# RPiEvm.net
KiCad netlist of a schematic drawn in EAGLE
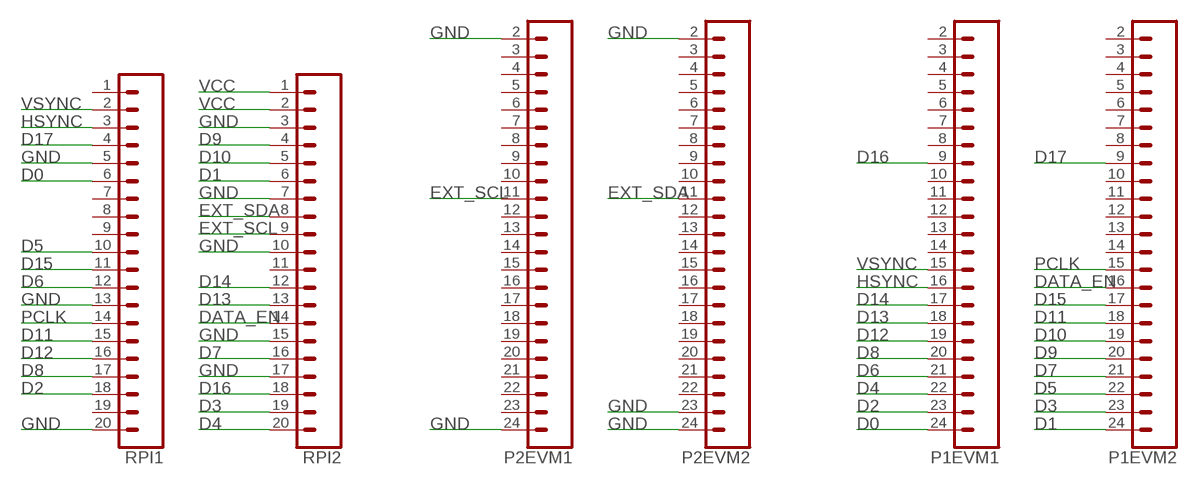
[diagram p0: schematic, sheet 1]

(export (version "E")
  (design (tool "Eeschema 10.0.6"))
  (components
    (comp (ref "P1EVM1")
      (value "CONN_23")
      (footprint "eagle-import:1X23")
      (libsource (lib "eagle-import") (part "CONN_23"))
    )
    (comp (ref "P1EVM2")
      (value "CONN_23")
      (footprint "eagle-import:1X23")
      (libsource (lib "eagle-import") (part "CONN_23"))
    )
    (comp (ref "P2EVM1")
      (value "CONN_23")
      (footprint "eagle-import:1X23")
      (libsource (lib "eagle-import") (part "CONN_23"))
    )
    (comp (ref "P2EVM2")
      (value "CONN_23")
      (footprint "eagle-import:1X23")
      (libsource (lib "eagle-import") (part "CONN_23"))
    )
    (comp (ref "RPI1")
      (value "CONN_20")
      (footprint "eagle-import:1X20")
      (libsource (lib "eagle-import") (part "CONN_20"))
    )
    (comp (ref "RPI2")
      (value "CONN_20")
      (footprint "eagle-import:1X20")
      (libsource (lib "eagle-import") (part "CONN_20"))
    )
  )
  (nets
    (net (code "1") (name "/D0") (class "Default")
      (node (ref "P1EVM1") (pin "24") (pinfunction "24_24") (pintype "passive"))
      (node (ref "RPI1") (pin "6") (pinfunction "6_6") (pintype "passive"))
    )
    (net (code "2") (name "/D1") (class "Default")
      (node (ref "P1EVM2") (pin "24") (pinfunction "24_24") (pintype "passive"))
      (node (ref "RPI2") (pin "6") (pinfunction "6_6") (pintype "passive"))
    )
    (net (code "3") (name "/D2") (class "Default")
      (node (ref "P1EVM1") (pin "23") (pinfunction "23_23") (pintype "passive"))
      (node (ref "RPI1") (pin "18") (pinfunction "18_18") (pintype "passive"))
    )
    (net (code "4") (name "/D3") (class "Default")
      (node (ref "P1EVM2") (pin "23") (pinfunction "23_23") (pintype "passive"))
      (node (ref "RPI2") (pin "19") (pinfunction "19_19") (pintype "passive"))
    )
    (net (code "5") (name "/D4") (class "Default")
      (node (ref "P1EVM1") (pin "22") (pinfunction "22_22") (pintype "passive"))
      (node (ref "RPI2") (pin "20") (pinfunction "20_20") (pintype "passive"))
    )
    (net (code "6") (name "/D5") (class "Default")
      (node (ref "P1EVM2") (pin "22") (pinfunction "22_22") (pintype "passive"))
      (node (ref "RPI1") (pin "10") (pinfunction "10_10") (pintype "passive"))
    )
    (net (code "7") (name "/D6") (class "Default")
      (node (ref "P1EVM1") (pin "21") (pinfunction "21_21") (pintype "passive"))
      (node (ref "RPI1") (pin "12") (pinfunction "12_12") (pintype "passive"))
    )
    (net (code "8") (name "/D7") (class "Default")
      (node (ref "P1EVM2") (pin "21") (pinfunction "21_21") (pintype "passive"))
      (node (ref "RPI2") (pin "16") (pinfunction "16_16") (pintype "passive"))
    )
    (net (code "9") (name "/D8") (class "Default")
      (node (ref "P1EVM1") (pin "20") (pinfunction "20_20") (pintype "passive"))
      (node (ref "RPI1") (pin "17") (pinfunction "17_17") (pintype "passive"))
    )
    (net (code "10") (name "/D9") (class "Default")
      (node (ref "P1EVM2") (pin "20") (pinfunction "20_20") (pintype "passive"))
      (node (ref "RPI2") (pin "4") (pinfunction "4_4") (pintype "passive"))
    )
    (net (code "11") (name "/D10") (class "Default")
      (node (ref "P1EVM2") (pin "19") (pinfunction "19_19") (pintype "passive"))
      (node (ref "RPI2") (pin "5") (pinfunction "5_5") (pintype "passive"))
    )
    (net (code "12") (name "/D11") (class "Default")
      (node (ref "P1EVM2") (pin "18") (pinfunction "18_18") (pintype "passive"))
      (node (ref "RPI1") (pin "15") (pinfunction "15_15") (pintype "passive"))
    )
    (net (code "13") (name "/D12") (class "Default")
      (node (ref "P1EVM1") (pin "19") (pinfunction "19_19") (pintype "passive"))
      (node (ref "RPI1") (pin "16") (pinfunction "16_16") (pintype "passive"))
    )
    (net (code "14") (name "/D13") (class "Default")
      (node (ref "P1EVM1") (pin "18") (pinfunction "18_18") (pintype "passive"))
      (node (ref "RPI2") (pin "13") (pinfunction "13_13") (pintype "passive"))
    )
    (net (code "15") (name "/D14") (class "Default")
      (node (ref "P1EVM1") (pin "17") (pinfunction "17_17") (pintype "passive"))
      (node (ref "RPI2") (pin "12") (pinfunction "12_12") (pintype "passive"))
    )
    (net (code "16") (name "/D15") (class "Default")
      (node (ref "P1EVM2") (pin "17") (pinfunction "17_17") (pintype "passive"))
      (node (ref "RPI1") (pin "11") (pinfunction "11_11") (pintype "passive"))
    )
    (net (code "17") (name "/D16") (class "Default")
      (node (ref "P1EVM1") (pin "9") (pinfunction "9_9") (pintype "passive"))
      (node (ref "RPI2") (pin "18") (pinfunction "18_18") (pintype "passive"))
    )
    (net (code "18") (name "/D17") (class "Default")
      (node (ref "P1EVM2") (pin "9") (pinfunction "9_9") (pintype "passive"))
      (node (ref "RPI1") (pin "4") (pinfunction "4_4") (pintype "passive"))
    )
    (net (code "19") (name "/DATA_EN") (class "Default")
      (node (ref "P1EVM2") (pin "16") (pinfunction "16_16") (pintype "passive"))
      (node (ref "RPI2") (pin "14") (pinfunction "14_14") (pintype "passive"))
    )
    (net (code "20") (name "/EXT_SCL") (class "Default")
      (node (ref "P2EVM1") (pin "11") (pinfunction "11_11") (pintype "passive"))
      (node (ref "RPI2") (pin "9") (pinfunction "9_9") (pintype "passive"))
    )
    (net (code "21") (name "/EXT_SDA") (class "Default")
      (node (ref "P2EVM2") (pin "11") (pinfunction "11_11") (pintype "passive"))
      (node (ref "RPI2") (pin "8") (pinfunction "8_8") (pintype "passive"))
    )
    (net (code "22") (name "/GND") (class "Default")
      (node (ref "P2EVM1") (pin "2") (pinfunction "2_2") (pintype "passive"))
      (node (ref "P2EVM1") (pin "24") (pinfunction "24_24") (pintype "passive"))
      (node (ref "P2EVM2") (pin "2") (pinfunction "2_2") (pintype "passive"))
      (node (ref "P2EVM2") (pin "23") (pinfunction "23_23") (pintype "passive"))
      (node (ref "P2EVM2") (pin "24") (pinfunction "24_24") (pintype "passive"))
      (node (ref "RPI1") (pin "13") (pinfunction "13_13") (pintype "passive"))
      (node (ref "RPI1") (pin "20") (pinfunction "20_20") (pintype "passive"))
      (node (ref "RPI1") (pin "5") (pinfunction "5_5") (pintype "passive"))
      (node (ref "RPI2") (pin "10") (pinfunction "10_10") (pintype "passive"))
      (node (ref "RPI2") (pin "15") (pinfunction "15_15") (pintype "passive"))
      (node (ref "RPI2") (pin "17") (pinfunction "17_17") (pintype "passive"))
      (node (ref "RPI2") (pin "3") (pinfunction "3_3") (pintype "passive"))
      (node (ref "RPI2") (pin "7") (pinfunction "7_7") (pintype "passive"))
    )
    (net (code "23") (name "/HSYNC") (class "Default")
      (node (ref "P1EVM1") (pin "16") (pinfunction "16_16") (pintype "passive"))
      (node (ref "RPI1") (pin "3") (pinfunction "3_3") (pintype "passive"))
    )
    (net (code "24") (name "/PCLK") (class "Default")
      (node (ref "P1EVM2") (pin "15") (pinfunction "15_15") (pintype "passive"))
      (node (ref "RPI1") (pin "14") (pinfunction "14_14") (pintype "passive"))
    )
    (net (code "25") (name "/VCC") (class "Default")
      (node (ref "RPI2") (pin "1") (pinfunction "1_1") (pintype "passive"))
      (node (ref "RPI2") (pin "2") (pinfunction "2_2") (pintype "passive"))
    )
    (net (code "26") (name "/VSYNC") (class "Default")
      (node (ref "P1EVM1") (pin "15") (pinfunction "15_15") (pintype "passive"))
      (node (ref "RPI1") (pin "2") (pinfunction "2_2") (pintype "passive"))
    )
    (net (code "27") (name "unconnected-(P1EVM1-Pad2)") (class "Default")
      (node (ref "P1EVM1") (pin "2") (pinfunction "2_2") (pintype "passive"))
    )
    (net (code "28") (name "unconnected-(P1EVM1-Pad3)") (class "Default")
      (node (ref "P1EVM1") (pin "3") (pinfunction "3_3") (pintype "passive"))
    )
    (net (code "29") (name "unconnected-(P1EVM1-Pad4)") (class "Default")
      (node (ref "P1EVM1") (pin "4") (pinfunction "4_4") (pintype "passive"))
    )
    (net (code "30") (name "unconnected-(P1EVM1-Pad5)") (class "Default")
      (node (ref "P1EVM1") (pin "5") (pinfunction "5_5") (pintype "passive"))
    )
    (net (code "31") (name "unconnected-(P1EVM1-Pad6)") (class "Default")
      (node (ref "P1EVM1") (pin "6") (pinfunction "6_6") (pintype "passive"))
    )
    (net (code "32") (name "unconnected-(P1EVM1-Pad7)") (class "Default")
      (node (ref "P1EVM1") (pin "7") (pinfunction "7_7") (pintype "passive"))
    )
    (net (code "33") (name "unconnected-(P1EVM1-Pad8)") (class "Default")
      (node (ref "P1EVM1") (pin "8") (pinfunction "8_8") (pintype "passive"))
    )
    (net (code "34") (name "unconnected-(P1EVM1-Pad10)") (class "Default")
      (node (ref "P1EVM1") (pin "10") (pinfunction "10_10") (pintype "passive"))
    )
    (net (code "35") (name "unconnected-(P1EVM1-Pad11)") (class "Default")
      (node (ref "P1EVM1") (pin "11") (pinfunction "11_11") (pintype "passive"))
    )
    (net (code "36") (name "unconnected-(P1EVM1-Pad12)") (class "Default")
      (node (ref "P1EVM1") (pin "12") (pinfunction "12_12") (pintype "passive"))
    )
    (net (code "37") (name "unconnected-(P1EVM1-Pad13)") (class "Default")
      (node (ref "P1EVM1") (pin "13") (pinfunction "13_13") (pintype "passive"))
    )
    (net (code "38") (name "unconnected-(P1EVM1-Pad14)") (class "Default")
      (node (ref "P1EVM1") (pin "14") (pinfunction "14_14") (pintype "passive"))
    )
    (net (code "39") (name "unconnected-(P1EVM2-Pad2)") (class "Default")
      (node (ref "P1EVM2") (pin "2") (pinfunction "2_2") (pintype "passive"))
    )
    (net (code "40") (name "unconnected-(P1EVM2-Pad3)") (class "Default")
      (node (ref "P1EVM2") (pin "3") (pinfunction "3_3") (pintype "passive"))
    )
    (net (code "41") (name "unconnected-(P1EVM2-Pad4)") (class "Default")
      (node (ref "P1EVM2") (pin "4") (pinfunction "4_4") (pintype "passive"))
    )
    (net (code "42") (name "unconnected-(P1EVM2-Pad5)") (class "Default")
      (node (ref "P1EVM2") (pin "5") (pinfunction "5_5") (pintype "passive"))
    )
    (net (code "43") (name "unconnected-(P1EVM2-Pad6)") (class "Default")
      (node (ref "P1EVM2") (pin "6") (pinfunction "6_6") (pintype "passive"))
    )
    (net (code "44") (name "unconnected-(P1EVM2-Pad7)") (class "Default")
      (node (ref "P1EVM2") (pin "7") (pinfunction "7_7") (pintype "passive"))
    )
    (net (code "45") (name "unconnected-(P1EVM2-Pad8)") (class "Default")
      (node (ref "P1EVM2") (pin "8") (pinfunction "8_8") (pintype "passive"))
    )
    (net (code "46") (name "unconnected-(P1EVM2-Pad10)") (class "Default")
      (node (ref "P1EVM2") (pin "10") (pinfunction "10_10") (pintype "passive"))
    )
    (net (code "47") (name "unconnected-(P1EVM2-Pad11)") (class "Default")
      (node (ref "P1EVM2") (pin "11") (pinfunction "11_11") (pintype "passive"))
    )
    (net (code "48") (name "unconnected-(P1EVM2-Pad12)") (class "Default")
      (node (ref "P1EVM2") (pin "12") (pinfunction "12_12") (pintype "passive"))
    )
    (net (code "49") (name "unconnected-(P1EVM2-Pad13)") (class "Default")
      (node (ref "P1EVM2") (pin "13") (pinfunction "13_13") (pintype "passive"))
    )
    (net (code "50") (name "unconnected-(P1EVM2-Pad14)") (class "Default")
      (node (ref "P1EVM2") (pin "14") (pinfunction "14_14") (pintype "passive"))
    )
    (net (code "51") (name "unconnected-(P2EVM1-Pad3)") (class "Default")
      (node (ref "P2EVM1") (pin "3") (pinfunction "3_3") (pintype "passive"))
    )
    (net (code "52") (name "unconnected-(P2EVM1-Pad4)") (class "Default")
      (node (ref "P2EVM1") (pin "4") (pinfunction "4_4") (pintype "passive"))
    )
    (net (code "53") (name "unconnected-(P2EVM1-Pad5)") (class "Default")
      (node (ref "P2EVM1") (pin "5") (pinfunction "5_5") (pintype "passive"))
    )
    (net (code "54") (name "unconnected-(P2EVM1-Pad6)") (class "Default")
      (node (ref "P2EVM1") (pin "6") (pinfunction "6_6") (pintype "passive"))
    )
    (net (code "55") (name "unconnected-(P2EVM1-Pad7)") (class "Default")
      (node (ref "P2EVM1") (pin "7") (pinfunction "7_7") (pintype "passive"))
    )
    (net (code "56") (name "unconnected-(P2EVM1-Pad8)") (class "Default")
      (node (ref "P2EVM1") (pin "8") (pinfunction "8_8") (pintype "passive"))
    )
    (net (code "57") (name "unconnected-(P2EVM1-Pad9)") (class "Default")
      (node (ref "P2EVM1") (pin "9") (pinfunction "9_9") (pintype "passive"))
    )
    (net (code "58") (name "unconnected-(P2EVM1-Pad10)") (class "Default")
      (node (ref "P2EVM1") (pin "10") (pinfunction "10_10") (pintype "passive"))
    )
    (net (code "59") (name "unconnected-(P2EVM1-Pad12)") (class "Default")
      (node (ref "P2EVM1") (pin "12") (pinfunction "12_12") (pintype "passive"))
    )
    (net (code "60") (name "unconnected-(P2EVM1-Pad13)") (class "Default")
      (node (ref "P2EVM1") (pin "13") (pinfunction "13_13") (pintype "passive"))
    )
    (net (code "61") (name "unconnected-(P2EVM1-Pad14)") (class "Default")
      (node (ref "P2EVM1") (pin "14") (pinfunction "14_14") (pintype "passive"))
    )
    (net (code "62") (name "unconnected-(P2EVM1-Pad15)") (class "Default")
      (node (ref "P2EVM1") (pin "15") (pinfunction "15_15") (pintype "passive"))
    )
    (net (code "63") (name "unconnected-(P2EVM1-Pad16)") (class "Default")
      (node (ref "P2EVM1") (pin "16") (pinfunction "16_16") (pintype "passive"))
    )
    (net (code "64") (name "unconnected-(P2EVM1-Pad17)") (class "Default")
      (node (ref "P2EVM1") (pin "17") (pinfunction "17_17") (pintype "passive"))
    )
    (net (code "65") (name "unconnected-(P2EVM1-Pad18)") (class "Default")
      (node (ref "P2EVM1") (pin "18") (pinfunction "18_18") (pintype "passive"))
    )
    (net (code "66") (name "unconnected-(P2EVM1-Pad19)") (class "Default")
      (node (ref "P2EVM1") (pin "19") (pinfunction "19_19") (pintype "passive"))
    )
    (net (code "67") (name "unconnected-(P2EVM1-Pad20)") (class "Default")
      (node (ref "P2EVM1") (pin "20") (pinfunction "20_20") (pintype "passive"))
    )
    (net (code "68") (name "unconnected-(P2EVM1-Pad21)") (class "Default")
      (node (ref "P2EVM1") (pin "21") (pinfunction "21_21") (pintype "passive"))
    )
    (net (code "69") (name "unconnected-(P2EVM1-Pad22)") (class "Default")
      (node (ref "P2EVM1") (pin "22") (pinfunction "22_22") (pintype "passive"))
    )
    (net (code "70") (name "unconnected-(P2EVM1-Pad23)") (class "Default")
      (node (ref "P2EVM1") (pin "23") (pinfunction "23_23") (pintype "passive"))
    )
    (net (code "71") (name "unconnected-(P2EVM2-Pad3)") (class "Default")
      (node (ref "P2EVM2") (pin "3") (pinfunction "3_3") (pintype "passive"))
    )
    (net (code "72") (name "unconnected-(P2EVM2-Pad4)") (class "Default")
      (node (ref "P2EVM2") (pin "4") (pinfunction "4_4") (pintype "passive"))
    )
    (net (code "73") (name "unconnected-(P2EVM2-Pad5)") (class "Default")
      (node (ref "P2EVM2") (pin "5") (pinfunction "5_5") (pintype "passive"))
    )
    (net (code "74") (name "unconnected-(P2EVM2-Pad6)") (class "Default")
      (node (ref "P2EVM2") (pin "6") (pinfunction "6_6") (pintype "passive"))
    )
    (net (code "75") (name "unconnected-(P2EVM2-Pad7)") (class "Default")
      (node (ref "P2EVM2") (pin "7") (pinfunction "7_7") (pintype "passive"))
    )
    (net (code "76") (name "unconnected-(P2EVM2-Pad8)") (class "Default")
      (node (ref "P2EVM2") (pin "8") (pinfunction "8_8") (pintype "passive"))
    )
    (net (code "77") (name "unconnected-(P2EVM2-Pad9)") (class "Default")
      (node (ref "P2EVM2") (pin "9") (pinfunction "9_9") (pintype "passive"))
    )
    (net (code "78") (name "unconnected-(P2EVM2-Pad10)") (class "Default")
      (node (ref "P2EVM2") (pin "10") (pinfunction "10_10") (pintype "passive"))
    )
    (net (code "79") (name "unconnected-(P2EVM2-Pad12)") (class "Default")
      (node (ref "P2EVM2") (pin "12") (pinfunction "12_12") (pintype "passive"))
    )
    (net (code "80") (name "unconnected-(P2EVM2-Pad13)") (class "Default")
      (node (ref "P2EVM2") (pin "13") (pinfunction "13_13") (pintype "passive"))
    )
    (net (code "81") (name "unconnected-(P2EVM2-Pad14)") (class "Default")
      (node (ref "P2EVM2") (pin "14") (pinfunction "14_14") (pintype "passive"))
    )
    (net (code "82") (name "unconnected-(P2EVM2-Pad15)") (class "Default")
      (node (ref "P2EVM2") (pin "15") (pinfunction "15_15") (pintype "passive"))
    )
    (net (code "83") (name "unconnected-(P2EVM2-Pad16)") (class "Default")
      (node (ref "P2EVM2") (pin "16") (pinfunction "16_16") (pintype "passive"))
    )
    (net (code "84") (name "unconnected-(P2EVM2-Pad17)") (class "Default")
      (node (ref "P2EVM2") (pin "17") (pinfunction "17_17") (pintype "passive"))
    )
    (net (code "85") (name "unconnected-(P2EVM2-Pad18)") (class "Default")
      (node (ref "P2EVM2") (pin "18") (pinfunction "18_18") (pintype "passive"))
    )
    (net (code "86") (name "unconnected-(P2EVM2-Pad19)") (class "Default")
      (node (ref "P2EVM2") (pin "19") (pinfunction "19_19") (pintype "passive"))
    )
    (net (code "87") (name "unconnected-(P2EVM2-Pad20)") (class "Default")
      (node (ref "P2EVM2") (pin "20") (pinfunction "20_20") (pintype "passive"))
    )
    (net (code "88") (name "unconnected-(P2EVM2-Pad21)") (class "Default")
      (node (ref "P2EVM2") (pin "21") (pinfunction "21_21") (pintype "passive"))
    )
    (net (code "89") (name "unconnected-(P2EVM2-Pad22)") (class "Default")
      (node (ref "P2EVM2") (pin "22") (pinfunction "22_22") (pintype "passive"))
    )
    (net (code "90") (name "unconnected-(RPI1-Pad1)") (class "Default")
      (node (ref "RPI1") (pin "1") (pinfunction "1_1") (pintype "passive"))
    )
    (net (code "91") (name "unconnected-(RPI1-Pad7)") (class "Default")
      (node (ref "RPI1") (pin "7") (pinfunction "7_7") (pintype "passive"))
    )
    (net (code "92") (name "unconnected-(RPI1-Pad8)") (class "Default")
      (node (ref "RPI1") (pin "8") (pinfunction "8_8") (pintype "passive"))
    )
    (net (code "93") (name "unconnected-(RPI1-Pad9)") (class "Default")
      (node (ref "RPI1") (pin "9") (pinfunction "9_9") (pintype "passive"))
    )
    (net (code "94") (name "unconnected-(RPI1-Pad19)") (class "Default")
      (node (ref "RPI1") (pin "19") (pinfunction "19_19") (pintype "passive"))
    )
    (net (code "95") (name "unconnected-(RPI2-Pad11)") (class "Default")
      (node (ref "RPI2") (pin "11") (pinfunction "11_11") (pintype "passive"))
    )
  )
)
